# IRtr.net
KiCad netlist of a schematic drawn in EAGLE
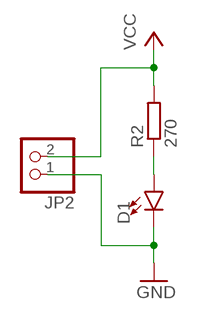
[diagram p0: schematic, sheet 1]

(export (version "E")
  (design (tool "Eeschema 10.0.6"))
  (components
    (comp (ref "D1")
      (value "LED-IRSIDE_EMITTER")
      (footprint "eagle-import:LTE-302")
      (libsource (lib "eagle-import") (part "LED-IRSIDE_EMITTER"))
    )
    (comp (ref "JP2")
      (value "PINHD-1X2")
      (footprint "eagle-import:1X02")
      (libsource (lib "eagle-import") (part "PINHD-1X2"))
    )
    (comp (ref "R2")
      (value "270")
      (footprint "eagle-import:R0805")
      (libsource (lib "eagle-import") (part "R-EU_R0805"))
    )
  )
  (nets
    (net (code "1") (name "GND") (class "Default")
      (node (ref "D1") (pin "C") (pinfunction "C_C") (pintype "passive"))
      (node (ref "JP2") (pin "1") (pinfunction "1_1") (pintype "passive"))
    )
    (net (code "2") (name "Net-(D1-PadA)") (class "Default")
      (node (ref "D1") (pin "A") (pinfunction "A_A") (pintype "passive"))
      (node (ref "R2") (pin "1") (pinfunction "1_1") (pintype "passive"))
    )
    (net (code "3") (name "VCC") (class "Default")
      (node (ref "JP2") (pin "2") (pinfunction "2_2") (pintype "passive"))
      (node (ref "R2") (pin "2") (pinfunction "2_2") (pintype "passive"))
    )
  )
)
